# Sheet1.net
KiCad netlist of a schematic drawn in Altium Designer
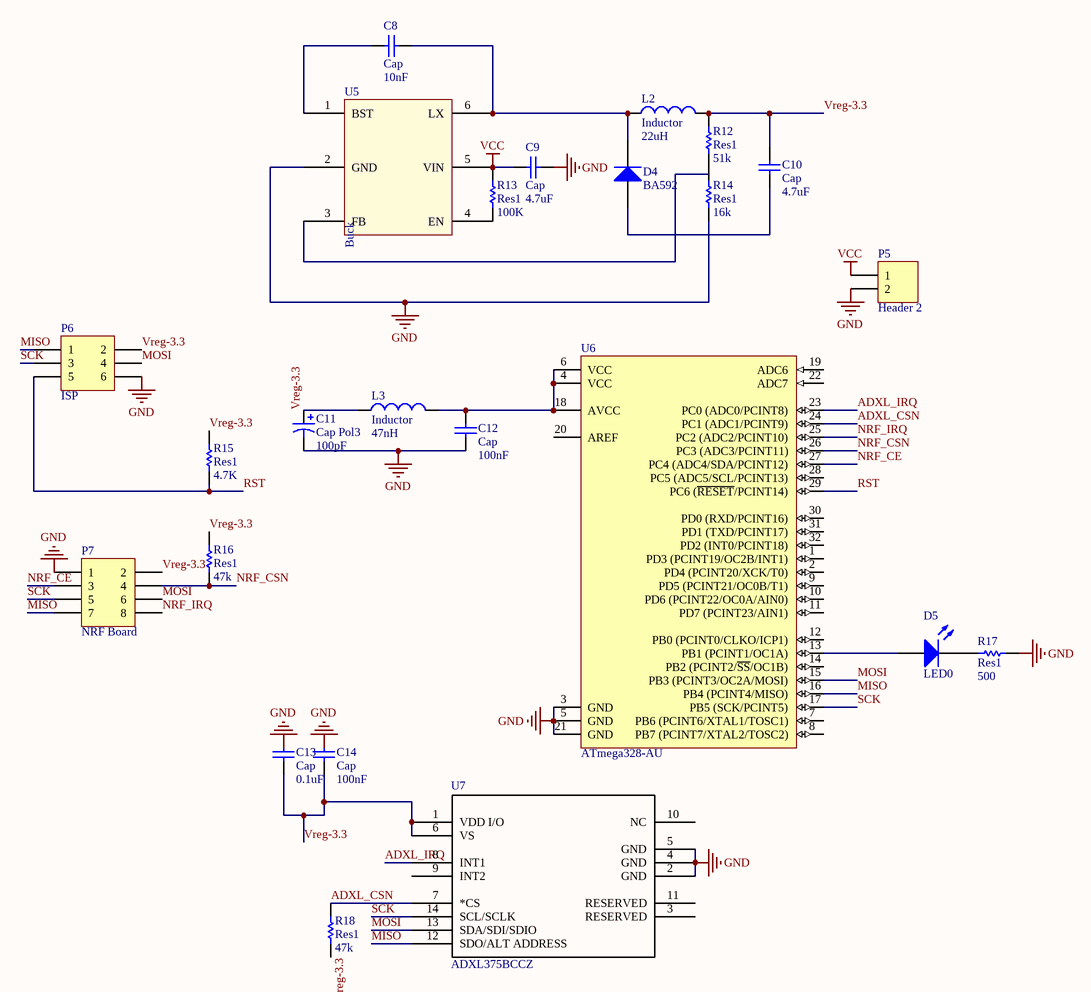
[diagram p0: Sheet1.SchDoc]

(export (version "E")
  (design (tool "Eeschema 10.0.6"))
  (components
    (comp (ref "C8")
      (value "Cap")
      (footprint "C0805")
      (description "Capacitor")
      (fields (field (name "ALTIUM_VALUE") "10nF") (field (name "PUBLISHER") "Altium Limited"))
      (libsource (lib "Miscellaneous Devices") (part "Cap"))
    )
    (comp (ref "C9")
      (value "Cap")
      (footprint "C0805")
      (description "Capacitor")
      (fields (field (name "ALTIUM_VALUE") "4.7uF") (field (name "PUBLISHER") "Altium Limited"))
      (libsource (lib "Miscellaneous Devices") (part "Cap"))
    )
    (comp (ref "C10")
      (value "Cap")
      (footprint "C0805")
      (description "Capacitor")
      (fields (field (name "ALTIUM_VALUE") "4.7uF") (field (name "PUBLISHER") "Altium Limited"))
      (libsource (lib "Miscellaneous Devices") (part "Cap"))
    )
    (comp (ref "C11")
      (value "Cap Pol3")
      (footprint "C0805")
      (description "Polarized Capacitor (Surface Mount)")
      (fields (field (name "ALTIUM_VALUE") "100pF") (field (name "PUBLISHER") "Altium Limited"))
      (libsource (lib "Miscellaneous Devices") (part "Cap Pol3"))
    )
    (comp (ref "C12")
      (value "Cap")
      (footprint "C0805")
      (description "Capacitor")
      (fields (field (name "ALTIUM_VALUE") "100nF") (field (name "PUBLISHER") "Altium Limited"))
      (libsource (lib "Miscellaneous Devices") (part "Cap"))
    )
    (comp (ref "C13")
      (value "Cap")
      (footprint "C0805")
      (description "Capacitor")
      (fields (field (name "ALTIUM_VALUE") "0.1uF") (field (name "PUBLISHER") "Altium Limited"))
      (libsource (lib "Miscellaneous Devices") (part "Cap"))
    )
    (comp (ref "C14")
      (value "Cap")
      (footprint "C0805")
      (description "Capacitor")
      (fields (field (name "ALTIUM_VALUE") "100nF") (field (name "PUBLISHER") "Altium Limited"))
      (libsource (lib "Miscellaneous Devices") (part "Cap"))
    )
    (comp (ref "D4")
      (value "BA592")
      (footprint "SOD-323")
      (description "Silicon RF Switching Diode for VHF Band Switching in TV/VTR Tuners")
      (fields (field (name "PUBLISHER") "Altium Limited"))
      (libsource (lib "Infineon Discrete Diode") (part "BA592"))
    )
    (comp (ref "D5")
      (value "LED0")
      (footprint "3.2X1.6X1.1")
      (description "Typical INFRARED GaAs LED")
      (fields (field (name "PUBLISHER") "Altium Limited"))
      (libsource (lib "Miscellaneous Devices") (part "LED0"))
    )
    (comp (ref "L2")
      (value "Inductor")
      (footprint "2029")
      (fields (field (name "ALTIUM_VALUE") "22uH") (field (name "PUBLISHER") "Altium Limited"))
      (libsource (lib "Miscellaneous Devices") (part "Inductor"))
    )
    (comp (ref "L3")
      (value "Inductor")
      (footprint "2029")
      (fields (field (name "ALTIUM_VALUE") "47nH") (field (name "PUBLISHER") "Altium Limited"))
      (libsource (lib "Miscellaneous Devices") (part "Inductor"))
    )
    (comp (ref "P5")
      (value "Header 2")
      (footprint "HDR1X2")
      (description "Header, 2-Pin")
      (fields (field (name "PUBLISHER") "Altium Limited"))
      (libsource (lib "Miscellaneous Connectors") (part "Header 2"))
    )
    (comp (ref "P6")
      (value "ISP")
      (footprint "HDR2X3")
      (description "Header, 3-Pin, Dual row")
      (fields (field (name "PUBLISHER") "Altium Limited"))
      (libsource (lib "Miscellaneous Connectors") (part "Header 3X2"))
    )
    (comp (ref "P7")
      (value "NRF Board")
      (footprint "HDR2X4")
      (description "Header, 4-Pin, Dual row")
      (fields (field (name "PUBLISHER") "Altium Limited"))
      (libsource (lib "Miscellaneous Connectors") (part "Header 4X2"))
    )
    (comp (ref "R12")
      (value "Res1")
      (footprint "6-0805_N")
      (description "Resistor")
      (fields (field (name "ALTIUM_VALUE") "51k") (field (name "PUBLISHER") "Altium Limited"))
      (libsource (lib "Miscellaneous Devices") (part "Res1"))
    )
    (comp (ref "R13")
      (value "Res1")
      (footprint "6-0805_N")
      (description "Resistor")
      (fields (field (name "ALTIUM_VALUE") "100K") (field (name "PUBLISHER") "Altium Limited"))
      (libsource (lib "Miscellaneous Devices") (part "Res1"))
    )
    (comp (ref "R14")
      (value "Res1")
      (footprint "6-0805_N")
      (description "Resistor")
      (fields (field (name "ALTIUM_VALUE") "16k") (field (name "PUBLISHER") "Altium Limited"))
      (libsource (lib "Miscellaneous Devices") (part "Res1"))
    )
    (comp (ref "R15")
      (value "Res1")
      (footprint "6-0805_N")
      (description "Resistor")
      (fields (field (name "ALTIUM_VALUE") "4.7K") (field (name "PUBLISHER") "Altium Limited"))
      (libsource (lib "Miscellaneous Devices") (part "Res1"))
    )
    (comp (ref "R16")
      (value "Res1")
      (footprint "6-0805_N")
      (description "Resistor")
      (fields (field (name "ALTIUM_VALUE") "47k") (field (name "PUBLISHER") "Altium Limited"))
      (libsource (lib "Miscellaneous Devices") (part "Res1"))
    )
    (comp (ref "R17")
      (value "Res1")
      (footprint "6-0805_N")
      (description "Resistor")
      (fields (field (name "ALTIUM_VALUE") "500") (field (name "PUBLISHER") "Altium Limited"))
      (libsource (lib "Miscellaneous Devices") (part "Res1"))
    )
    (comp (ref "R18")
      (value "Res1")
      (footprint "6-0805_N")
      (description "Resistor")
      (fields (field (name "ALTIUM_VALUE") "47k") (field (name "PUBLISHER") "Altium Limited"))
      (libsource (lib "Miscellaneous Devices") (part "Res1"))
    )
    (comp (ref "U5") (value "Buck") (footprint "SOT23-6") (libsource (lib "aoz1280ci") (part "Component_1")))
    (comp (ref "U6")
      (value "ATmega328-AU")
      (footprint "32A_N")
      (fields (field (name "PUBLISHER") "Altium Limited"))
      (libsource (lib "Atmel Microcontroller 8-Bit megaAVR") (part "ATmega328-AU"))
    )
    (comp (ref "U7")
      (value "ADXL375BCCZ")
      (footprint "LGA_CC-14-1")
      (description "Imported")
      (libsource (lib "ADXL345") (part "ADXL345BCCZ"))
    )
  )
  (nets
    (net (code "1") (name "/ADXL_CSN") (class "Default")
      (node (ref "R18") (pin "2") (pinfunction "2_2") (pintype "passive"))
      (node (ref "U6") (pin "24") (pinfunction "PC1_(ADC1/PCINT9)_24") (pintype "bidirectional"))
      (node (ref "U7") (pin "7") (pinfunction "*CS_7") (pintype "passive"))
    )
    (net (code "2") (name "/ADXL_IRQ") (class "Default")
      (node (ref "U6") (pin "23") (pinfunction "PC0_(ADC0/PCINT8)_23") (pintype "bidirectional"))
      (node (ref "U7") (pin "8") (pinfunction "INT1_8") (pintype "passive"))
    )
    (net (code "3") (name "/MISO") (class "Default")
      (node (ref "P6") (pin "1") (pinfunction "1_1") (pintype "passive"))
      (node (ref "P7") (pin "7") (pinfunction "7_7") (pintype "passive"))
      (node (ref "U6") (pin "16") (pinfunction "PB4_(PCINT4/MISO)_16") (pintype "bidirectional"))
      (node (ref "U7") (pin "12") (pinfunction "SDO/ALT_ADDRESS_12") (pintype "passive"))
    )
    (net (code "4") (name "/MOSI") (class "Default")
      (node (ref "P6") (pin "4") (pinfunction "4_4") (pintype "passive"))
      (node (ref "P7") (pin "6") (pinfunction "6_6") (pintype "passive"))
      (node (ref "U6") (pin "15") (pinfunction "PB3_(PCINT3/OC2A/MOSI)_15") (pintype "bidirectional"))
      (node (ref "U7") (pin "13") (pinfunction "SDA/SDI/SDIO_13") (pintype "passive"))
    )
    (net (code "5") (name "/NRF_CE") (class "Default")
      (node (ref "P7") (pin "3") (pinfunction "3_3") (pintype "passive"))
      (node (ref "U6") (pin "27") (pinfunction "PC4_(ADC4/SDA/PCINT12)_27") (pintype "bidirectional"))
    )
    (net (code "6") (name "/NRF_CSN") (class "Default")
      (node (ref "P7") (pin "4") (pinfunction "4_4") (pintype "passive"))
      (node (ref "R16") (pin "1") (pinfunction "1_1") (pintype "passive"))
      (node (ref "U6") (pin "26") (pinfunction "PC3_(ADC3/PCINT11)_26") (pintype "bidirectional"))
    )
    (net (code "7") (name "/NRF_IRQ") (class "Default")
      (node (ref "P7") (pin "8") (pinfunction "8_8") (pintype "passive"))
      (node (ref "U6") (pin "25") (pinfunction "PC2_(ADC2/PCINT10)_25") (pintype "bidirectional"))
    )
    (net (code "8") (name "/RST") (class "Default")
      (node (ref "P6") (pin "5") (pinfunction "5_5") (pintype "passive"))
      (node (ref "R15") (pin "1") (pinfunction "1_1") (pintype "passive"))
      (node (ref "U6") (pin "29") (pinfunction "PC6_(~{RESET}/PCINT14)_29") (pintype "bidirectional"))
    )
    (net (code "9") (name "/SCK") (class "Default")
      (node (ref "P6") (pin "3") (pinfunction "3_3") (pintype "passive"))
      (node (ref "P7") (pin "5") (pinfunction "5_5") (pintype "passive"))
      (node (ref "U6") (pin "17") (pinfunction "PB5_(SCK/PCINT5)_17") (pintype "bidirectional"))
      (node (ref "U7") (pin "14") (pinfunction "SCL/SCLK_14") (pintype "passive"))
    )
    (net (code "10") (name "/Vreg-3.3") (class "Default")
      (node (ref "C10") (pin "2") (pinfunction "2_2") (pintype "passive"))
      (node (ref "C11") (pin "1") (pinfunction "1_1") (pintype "passive"))
      (node (ref "C13") (pin "1") (pinfunction "1_1") (pintype "passive"))
      (node (ref "C14") (pin "1") (pinfunction "1_1") (pintype "passive"))
      (node (ref "L2") (pin "2") (pinfunction "2_2") (pintype "passive"))
      (node (ref "L3") (pin "1") (pinfunction "1_1") (pintype "passive"))
      (node (ref "P6") (pin "2") (pinfunction "2_2") (pintype "passive"))
      (node (ref "P7") (pin "2") (pinfunction "2_2") (pintype "passive"))
      (node (ref "R12") (pin "2") (pinfunction "2_2") (pintype "passive"))
      (node (ref "R15") (pin "2") (pinfunction "2_2") (pintype "passive"))
      (node (ref "R16") (pin "2") (pinfunction "2_2") (pintype "passive"))
      (node (ref "R18") (pin "1") (pinfunction "1_1") (pintype "passive"))
      (node (ref "U7") (pin "1") (pinfunction "VDD_I/O_1") (pintype "passive"))
      (node (ref "U7") (pin "6") (pinfunction "VS_6") (pintype "passive"))
    )
    (net (code "11") (name "GND") (class "Default")
      (node (ref "C11") (pin "2") (pinfunction "2_2") (pintype "passive"))
      (node (ref "C12") (pin "1") (pinfunction "1_1") (pintype "passive"))
      (node (ref "C9") (pin "1") (pinfunction "1_1") (pintype "passive"))
      (node (ref "P5") (pin "2") (pinfunction "2_2") (pintype "passive"))
      (node (ref "P6") (pin "6") (pinfunction "6_6") (pintype "passive"))
      (node (ref "P7") (pin "1") (pinfunction "1_1") (pintype "passive"))
      (node (ref "R14") (pin "1") (pinfunction "1_1") (pintype "passive"))
      (node (ref "R17") (pin "2") (pinfunction "2_2") (pintype "passive"))
      (node (ref "U5") (pin "2") (pinfunction "GND_2") (pintype "passive"))
      (node (ref "U6") (pin "21") (pinfunction "GND_21") (pintype "power_in"))
      (node (ref "U6") (pin "3") (pinfunction "GND_3") (pintype "power_in"))
      (node (ref "U6") (pin "5") (pinfunction "GND_5") (pintype "power_in"))
      (node (ref "U7") (pin "2") (pinfunction "GND_2") (pintype "passive"))
      (node (ref "U7") (pin "4") (pinfunction "GND_4") (pintype "passive"))
      (node (ref "U7") (pin "5") (pinfunction "GND_5") (pintype "passive"))
    )
    (net (code "12") (name "Net-(D4-A)") (class "Default")
      (node (ref "C10") (pin "1") (pinfunction "1_1") (pintype "passive"))
      (node (ref "D4") (pin "2") (pinfunction "A_2") (pintype "passive"))
    )
    (net (code "13") (name "Net-(D4-K)") (class "Default")
      (node (ref "C8") (pin "1") (pinfunction "1_1") (pintype "passive"))
      (node (ref "D4") (pin "1") (pinfunction "K_1") (pintype "passive"))
      (node (ref "L2") (pin "1") (pinfunction "1_1") (pintype "passive"))
      (node (ref "U5") (pin "6") (pinfunction "LX_6") (pintype "passive"))
    )
    (net (code "14") (name "Net-(D5-A)") (class "Default")
      (node (ref "D5") (pin "1") (pinfunction "A_1") (pintype "passive"))
      (node (ref "U6") (pin "13") (pinfunction "PB1_(PCINT1/OC1A)_13") (pintype "bidirectional"))
    )
    (net (code "15") (name "Net-(D5-K)") (class "Default")
      (node (ref "D5") (pin "2") (pinfunction "K_2") (pintype "passive"))
      (node (ref "R17") (pin "1") (pinfunction "1_1") (pintype "passive"))
    )
    (net (code "16") (name "Net-(R12-Pad1)") (class "Default")
      (node (ref "R12") (pin "1") (pinfunction "1_1") (pintype "passive"))
      (node (ref "R14") (pin "2") (pinfunction "2_2") (pintype "passive"))
    )
    (net (code "17") (name "Net-(U5-BST)") (class "Default")
      (node (ref "C8") (pin "2") (pinfunction "2_2") (pintype "passive"))
      (node (ref "U5") (pin "1") (pinfunction "BST_1") (pintype "passive"))
    )
    (net (code "18") (name "Net-(U5-EN)") (class "Default")
      (node (ref "R13") (pin "1") (pinfunction "1_1") (pintype "passive"))
      (node (ref "U5") (pin "4") (pinfunction "EN_4") (pintype "passive"))
    )
    (net (code "19") (name "Net-(U6-AVCC)") (class "Default")
      (node (ref "C12") (pin "2") (pinfunction "2_2") (pintype "passive"))
      (node (ref "L3") (pin "2") (pinfunction "2_2") (pintype "passive"))
      (node (ref "U6") (pin "18") (pinfunction "AVCC_18") (pintype "power_in"))
      (node (ref "U6") (pin "4") (pinfunction "VCC_4") (pintype "power_in"))
      (node (ref "U6") (pin "6") (pinfunction "VCC_6") (pintype "power_in"))
    )
    (net (code "20") (name "VCC") (class "Default")
      (node (ref "C9") (pin "2") (pinfunction "2_2") (pintype "passive"))
      (node (ref "P5") (pin "1") (pinfunction "1_1") (pintype "passive"))
      (node (ref "R13") (pin "2") (pinfunction "2_2") (pintype "passive"))
      (node (ref "U5") (pin "5") (pinfunction "VIN_5") (pintype "passive"))
    )
    (net (code "21") (name "unconnected-(C13-Pad2)") (class "Default")
      (node (ref "C13") (pin "2") (pinfunction "2_2") (pintype "passive"))
    )
    (net (code "22") (name "unconnected-(C14-Pad2)") (class "Default")
      (node (ref "C14") (pin "2") (pinfunction "2_2") (pintype "passive"))
    )
    (net (code "23") (name "unconnected-(U5-FB-Pad3)") (class "Default")
      (node (ref "U5") (pin "3") (pinfunction "FB_3") (pintype "passive"))
    )
    (net (code "24") (name "unconnected-(U6-ADC6-Pad19)") (class "Default")
      (node (ref "U6") (pin "19") (pinfunction "ADC6_19") (pintype "input"))
    )
    (net (code "25") (name "unconnected-(U6-ADC7-Pad22)") (class "Default")
      (node (ref "U6") (pin "22") (pinfunction "ADC7_22") (pintype "input"))
    )
    (net (code "26") (name "unconnected-(U6-AREF-Pad20)") (class "Default")
      (node (ref "U6") (pin "20") (pinfunction "AREF_20") (pintype "passive"))
    )
    (net (code "27") (name "unconnected-(U6-PB0_(PCINT0{slash}CLKO{slash}ICP1)-Pad12)") (class "Default")
      (node (ref "U6") (pin "12") (pinfunction "PB0_(PCINT0/CLKO/ICP1)_12") (pintype "bidirectional"))
    )
    (net (code "28") (name "unconnected-(U6-PB2_(PCINT2{slash}~{SS}{slash}OC1B)-Pad14)") (class "Default")
      (node (ref "U6") (pin "14") (pinfunction "PB2_(PCINT2/~{SS}/OC1B)_14") (pintype "bidirectional"))
    )
    (net (code "29") (name "unconnected-(U6-PB6_(PCINT6{slash}XTAL1{slash}TOSC1)-Pad7)") (class "Default")
      (node (ref "U6") (pin "7") (pinfunction "PB6_(PCINT6/XTAL1/TOSC1)_7") (pintype "bidirectional"))
    )
    (net (code "30") (name "unconnected-(U6-PB7_(PCINT7{slash}XTAL2{slash}TOSC2)-Pad8)") (class "Default")
      (node (ref "U6") (pin "8") (pinfunction "PB7_(PCINT7/XTAL2/TOSC2)_8") (pintype "bidirectional"))
    )
    (net (code "31") (name "unconnected-(U6-PC5_(ADC5{slash}SCL{slash}PCINT13)-Pad28)") (class "Default")
      (node (ref "U6") (pin "28") (pinfunction "PC5_(ADC5/SCL/PCINT13)_28") (pintype "bidirectional"))
    )
    (net (code "32") (name "unconnected-(U6-PD0_(RXD{slash}PCINT16)-Pad30)") (class "Default")
      (node (ref "U6") (pin "30") (pinfunction "PD0_(RXD/PCINT16)_30") (pintype "bidirectional"))
    )
    (net (code "33") (name "unconnected-(U6-PD1_(TXD{slash}PCINT17)-Pad31)") (class "Default")
      (node (ref "U6") (pin "31") (pinfunction "PD1_(TXD/PCINT17)_31") (pintype "bidirectional"))
    )
    (net (code "34") (name "unconnected-(U6-PD2_(INT0{slash}PCINT18)-Pad32)") (class "Default")
      (node (ref "U6") (pin "32") (pinfunction "PD2_(INT0/PCINT18)_32") (pintype "bidirectional"))
    )
    (net (code "35") (name "unconnected-(U6-PD3_(PCINT19{slash}OC2B{slash}INT1)-Pad1)") (class "Default")
      (node (ref "U6") (pin "1") (pinfunction "PD3_(PCINT19/OC2B/INT1)_1") (pintype "bidirectional"))
    )
    (net (code "36") (name "unconnected-(U6-PD4_(PCINT20{slash}XCK{slash}T0)-Pad2)") (class "Default")
      (node (ref "U6") (pin "2") (pinfunction "PD4_(PCINT20/XCK/T0)_2") (pintype "bidirectional"))
    )
    (net (code "37") (name "unconnected-(U6-PD5_(PCINT21{slash}OC0B{slash}T1)-Pad9)") (class "Default")
      (node (ref "U6") (pin "9") (pinfunction "PD5_(PCINT21/OC0B/T1)_9") (pintype "bidirectional"))
    )
    (net (code "38") (name "unconnected-(U6-PD6_(PCINT22{slash}OC0A{slash}AIN0)-Pad10)") (class "Default")
      (node (ref "U6") (pin "10") (pinfunction "PD6_(PCINT22/OC0A/AIN0)_10") (pintype "bidirectional"))
    )
    (net (code "39") (name "unconnected-(U6-PD7_(PCINT23{slash}AIN1)-Pad11)") (class "Default")
      (node (ref "U6") (pin "11") (pinfunction "PD7_(PCINT23/AIN1)_11") (pintype "bidirectional"))
    )
    (net (code "40") (name "unconnected-(U7-INT2-Pad9)") (class "Default")
      (node (ref "U7") (pin "9") (pinfunction "INT2_9") (pintype "passive"))
    )
    (net (code "41") (name "unconnected-(U7-NC-Pad10)") (class "Default")
      (node (ref "U7") (pin "10") (pinfunction "NC_10") (pintype "passive"))
    )
    (net (code "42") (name "unconnected-(U7-RESERVED-Pad3)") (class "Default")
      (node (ref "U7") (pin "3") (pinfunction "RESERVED_3") (pintype "passive"))
    )
    (net (code "43") (name "unconnected-(U7-RESERVED-Pad11)") (class "Default")
      (node (ref "U7") (pin "11") (pinfunction "RESERVED_11") (pintype "passive"))
    )
  )
)
